# BreadBoard_Power_Supply_DC_5V_3_3V.net
KiCad netlist of a schematic drawn in EAGLE
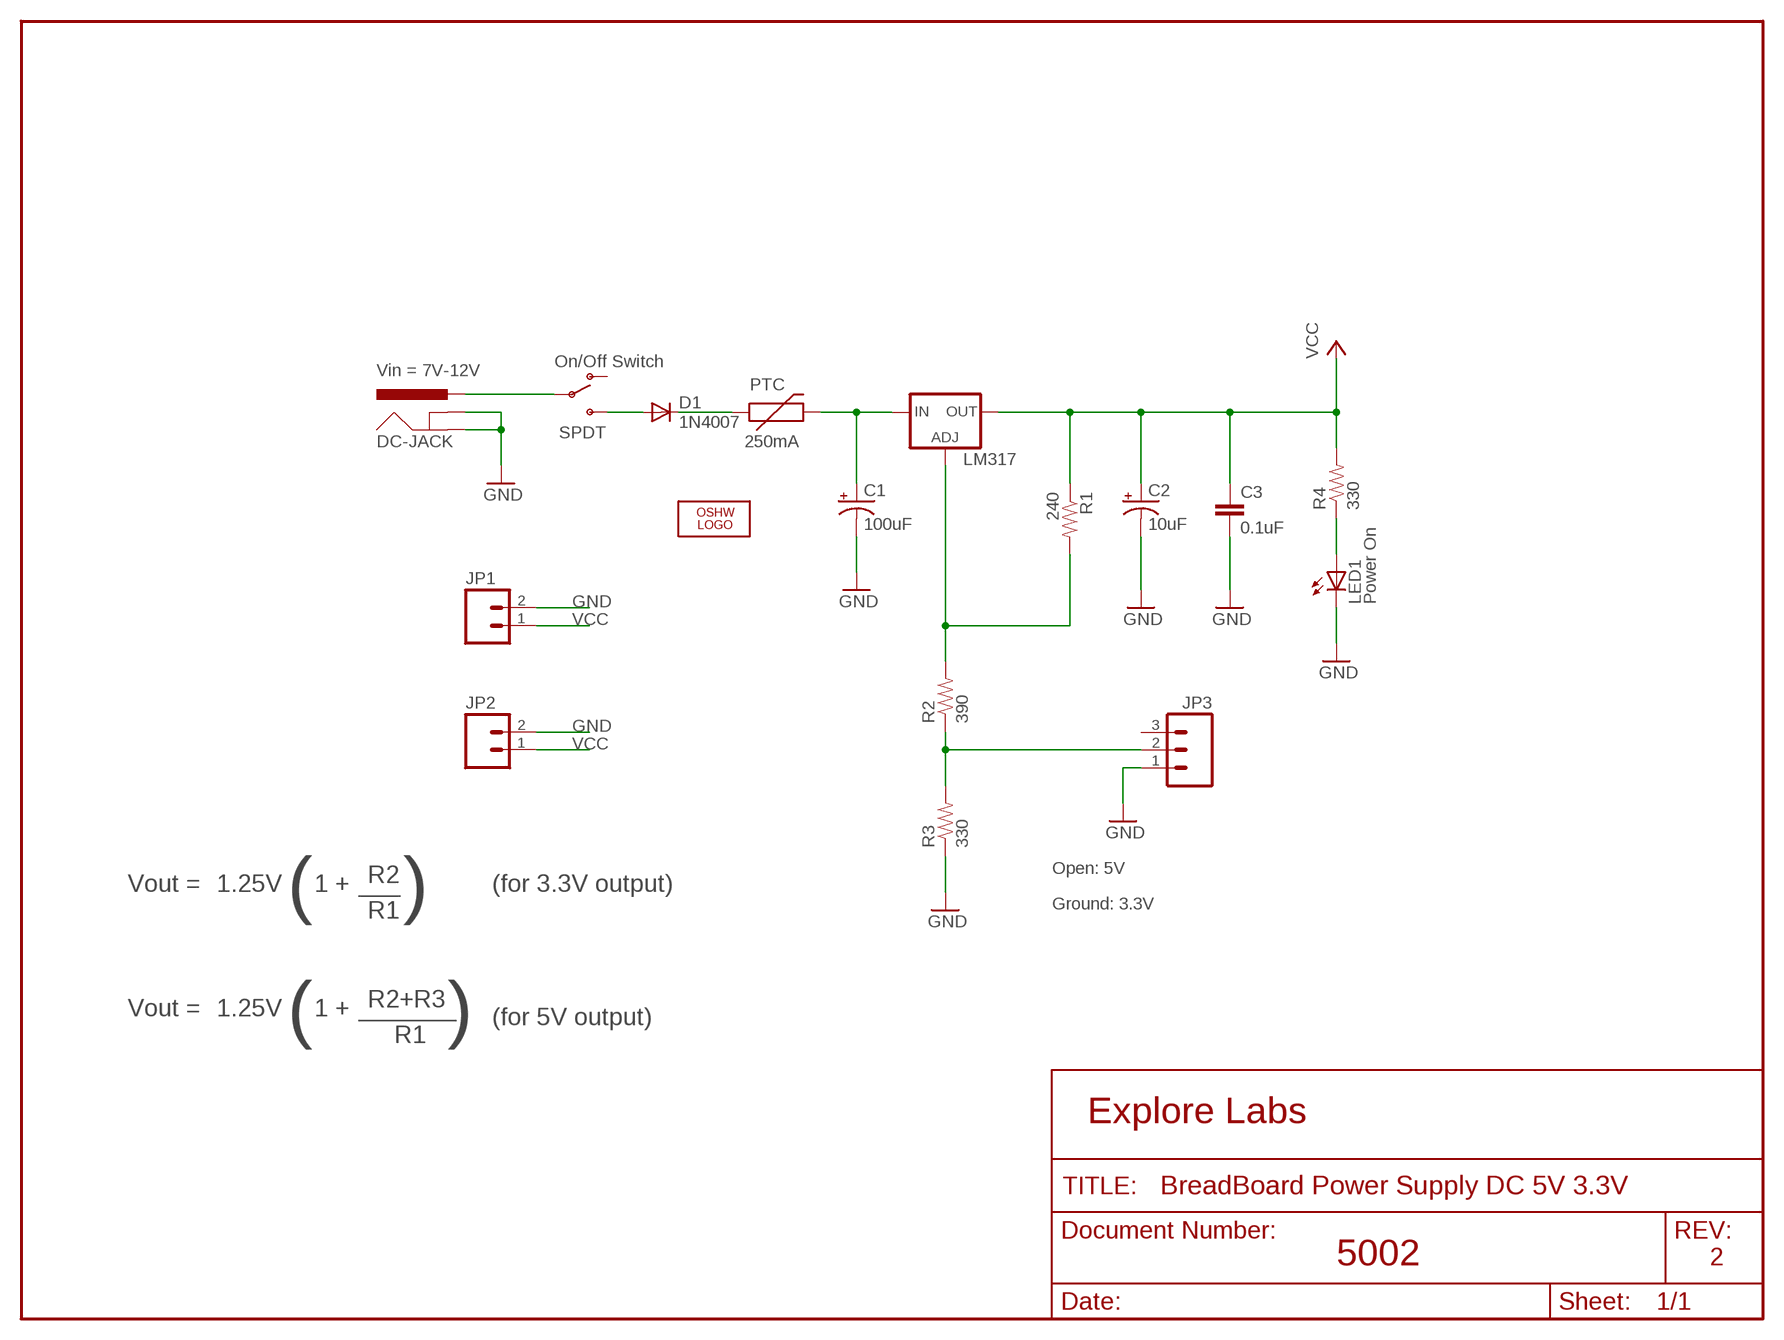
[diagram p0: schematic, sheet 1]

(export (version "E")
  (design (tool "Eeschema 10.0.6"))
  (components
    (comp (ref "C1")
      (value "100uF")
      (footprint "eagle-import:CPOL-RADIAL-10UF-25V")
      (libsource (lib "eagle-import") (part "CAP_POLPTH2"))
    )
    (comp (ref "C2")
      (value "10uF")
      (footprint "eagle-import:CPOL-RADIAL-10UF-25V")
      (libsource (lib "eagle-import") (part "CAP_POLPTH2"))
    )
    (comp (ref "C3")
      (value "0.1uF")
      (footprint "eagle-import:CAP-PTH-SMALL")
      (libsource (lib "eagle-import") (part "CAPPTH"))
    )
    (comp (ref "D1")
      (value "1N4007")
      (footprint "eagle-import:DIODE-1N4148")
      (libsource (lib "eagle-import") (part "DIODE1N4148"))
    )
    (comp (ref "DC-JACK")
      (value "Vin = 7V-12V")
      (footprint "eagle-import:POWER_JACK_PTH")
      (libsource (lib "eagle-import") (part "POWER_JACKPTH"))
    )
    (comp (ref "JP1")
      (value "M02PTH")
      (footprint "eagle-import:1X02")
      (libsource (lib "eagle-import") (part "M02PTH"))
    )
    (comp (ref "JP2")
      (value "M02PTH")
      (footprint "eagle-import:1X02")
      (libsource (lib "eagle-import") (part "M02PTH"))
    )
    (comp (ref "JP3")
      (value "M03PTH")
      (footprint "eagle-import:1X03")
      (libsource (lib "eagle-import") (part "M03PTH"))
    )
    (comp (ref "LED1")
      (value "Power On")
      (footprint "eagle-import:LED5MM")
      (libsource (lib "eagle-import") (part "LED5MM"))
    )
    (comp (ref "LM317")
      (value "LM317TS")
      (footprint "eagle-import:317TS")
      (libsource (lib "eagle-import") (part "LM317TS"))
    )
    (comp (ref "LOGO1")
      (value "OSHW_LOGO_8MILX0150-NT")
      (footprint "eagle-import:OSHW_8X150_NOTEXT")
      (libsource (lib "eagle-import") (part "OSHW_LOGO_8MILX0150-NT"))
    )
    (comp (ref "PTC")
      (value "250mA")
      (footprint "eagle-import:PTC")
      (libsource (lib "eagle-import") (part "PTCPTH"))
    )
    (comp (ref "R1")
      (value "240")
      (footprint "eagle-import:AXIAL-0.3")
      (libsource (lib "eagle-import") (part "RESISTORPTH1"))
    )
    (comp (ref "R2")
      (value "390")
      (footprint "eagle-import:AXIAL-0.3")
      (libsource (lib "eagle-import") (part "RESISTORPTH1"))
    )
    (comp (ref "R3")
      (value "330")
      (footprint "eagle-import:AXIAL-0.3")
      (libsource (lib "eagle-import") (part "RESISTORPTH1"))
    )
    (comp (ref "R4")
      (value "330")
      (footprint "eagle-import:AXIAL-0.3")
      (libsource (lib "eagle-import") (part "RESISTORPTH1"))
    )
    (comp (ref "SPDT")
      (value "On/Off Switch")
      (footprint "eagle-import:SWITCH-SPDT")
      (libsource (lib "eagle-import") (part "SWITCH-SPSTPTH"))
    )
  )
  (nets
    (net (code "1") (name "GND") (class "Default")
      (node (ref "C1") (pin "2") (pinfunction "-_2") (pintype "passive"))
      (node (ref "C2") (pin "2") (pinfunction "-_2") (pintype "passive"))
      (node (ref "C3") (pin "2") (pinfunction "2_2") (pintype "passive"))
      (node (ref "DC-JACK") (pin "GND") (pinfunction "GND_GND") (pintype "bidirectional"))
      (node (ref "DC-JACK") (pin "GNDBREAK") (pinfunction "GNDBREAK_GNDBREAK") (pintype "bidirectional"))
      (node (ref "JP1") (pin "2") (pinfunction "2_2") (pintype "passive"))
      (node (ref "JP2") (pin "2") (pinfunction "2_2") (pintype "passive"))
      (node (ref "JP3") (pin "1") (pinfunction "1_1") (pintype "passive"))
      (node (ref "LED1") (pin "K") (pinfunction "C_K") (pintype "passive"))
      (node (ref "R3") (pin "P$1") (pinfunction "1_P$1") (pintype "passive"))
    )
    (net (code "2") (name "Net-(C1-+)") (class "Default")
      (node (ref "C1") (pin "1") (pinfunction "+_1") (pintype "passive"))
      (node (ref "LM317") (pin "3") (pinfunction "IN_3") (pintype "input"))
      (node (ref "PTC") (pin "P$2") (pinfunction "2_P$2") (pintype "bidirectional"))
    )
    (net (code "3") (name "Net-(LM317-ADJ)") (class "Default")
      (node (ref "LM317") (pin "1") (pinfunction "ADJ_1") (pintype "input"))
      (node (ref "R1") (pin "P$2") (pinfunction "2_P$2") (pintype "passive"))
      (node (ref "R2") (pin "P$2") (pinfunction "2_P$2") (pintype "passive"))
    )
    (net (code "4") (name "Net-(PTC-1)") (class "Default")
      (node (ref "D1") (pin "C") (pinfunction "C_C") (pintype "passive"))
      (node (ref "PTC") (pin "P$1") (pinfunction "1_P$1") (pintype "bidirectional"))
    )
    (net (code "5") (name "Net-(R2-1)") (class "Default")
      (node (ref "JP3") (pin "2") (pinfunction "2_2") (pintype "passive"))
      (node (ref "R2") (pin "P$1") (pinfunction "1_P$1") (pintype "passive"))
      (node (ref "R3") (pin "P$2") (pinfunction "2_P$2") (pintype "passive"))
    )
    (net (code "6") (name "Net-(R4-1)") (class "Default")
      (node (ref "LED1") (pin "A") (pinfunction "A_A") (pintype "passive"))
      (node (ref "R4") (pin "P$1") (pinfunction "1_P$1") (pintype "passive"))
    )
    (net (code "7") (name "Net-(SPDT-P)") (class "Default")
      (node (ref "DC-JACK") (pin "PWR") (pinfunction "PWR_PWR") (pintype "bidirectional"))
      (node (ref "SPDT") (pin "2") (pinfunction "P_2") (pintype "passive"))
    )
    (net (code "8") (name "Net-(SPDT-S)") (class "Default")
      (node (ref "D1") (pin "A") (pinfunction "A_A") (pintype "passive"))
      (node (ref "SPDT") (pin "3") (pinfunction "S_3") (pintype "passive"))
    )
    (net (code "9") (name "VCC") (class "Default")
      (node (ref "C2") (pin "1") (pinfunction "+_1") (pintype "passive"))
      (node (ref "C3") (pin "1") (pinfunction "1_1") (pintype "passive"))
      (node (ref "JP1") (pin "1") (pinfunction "1_1") (pintype "passive"))
      (node (ref "JP2") (pin "1") (pinfunction "1_1") (pintype "passive"))
      (node (ref "LM317") (pin "2") (pinfunction "OUT_2") (pintype "passive"))
      (node (ref "R1") (pin "P$1") (pinfunction "1_P$1") (pintype "passive"))
      (node (ref "R4") (pin "P$2") (pinfunction "2_P$2") (pintype "passive"))
    )
    (net (code "10") (name "unconnected-(JP3-Pad3)") (class "Default")
      (node (ref "JP3") (pin "3") (pinfunction "3_3") (pintype "passive"))
    )
    (net (code "11") (name "unconnected-(SPDT-O-Pad1)") (class "Default")
      (node (ref "SPDT") (pin "1") (pinfunction "O_1") (pintype "passive"))
    )
  )
)
